# CarteCapteurAvant3.net
KiCad netlist of a schematic drawn in Altium Designer
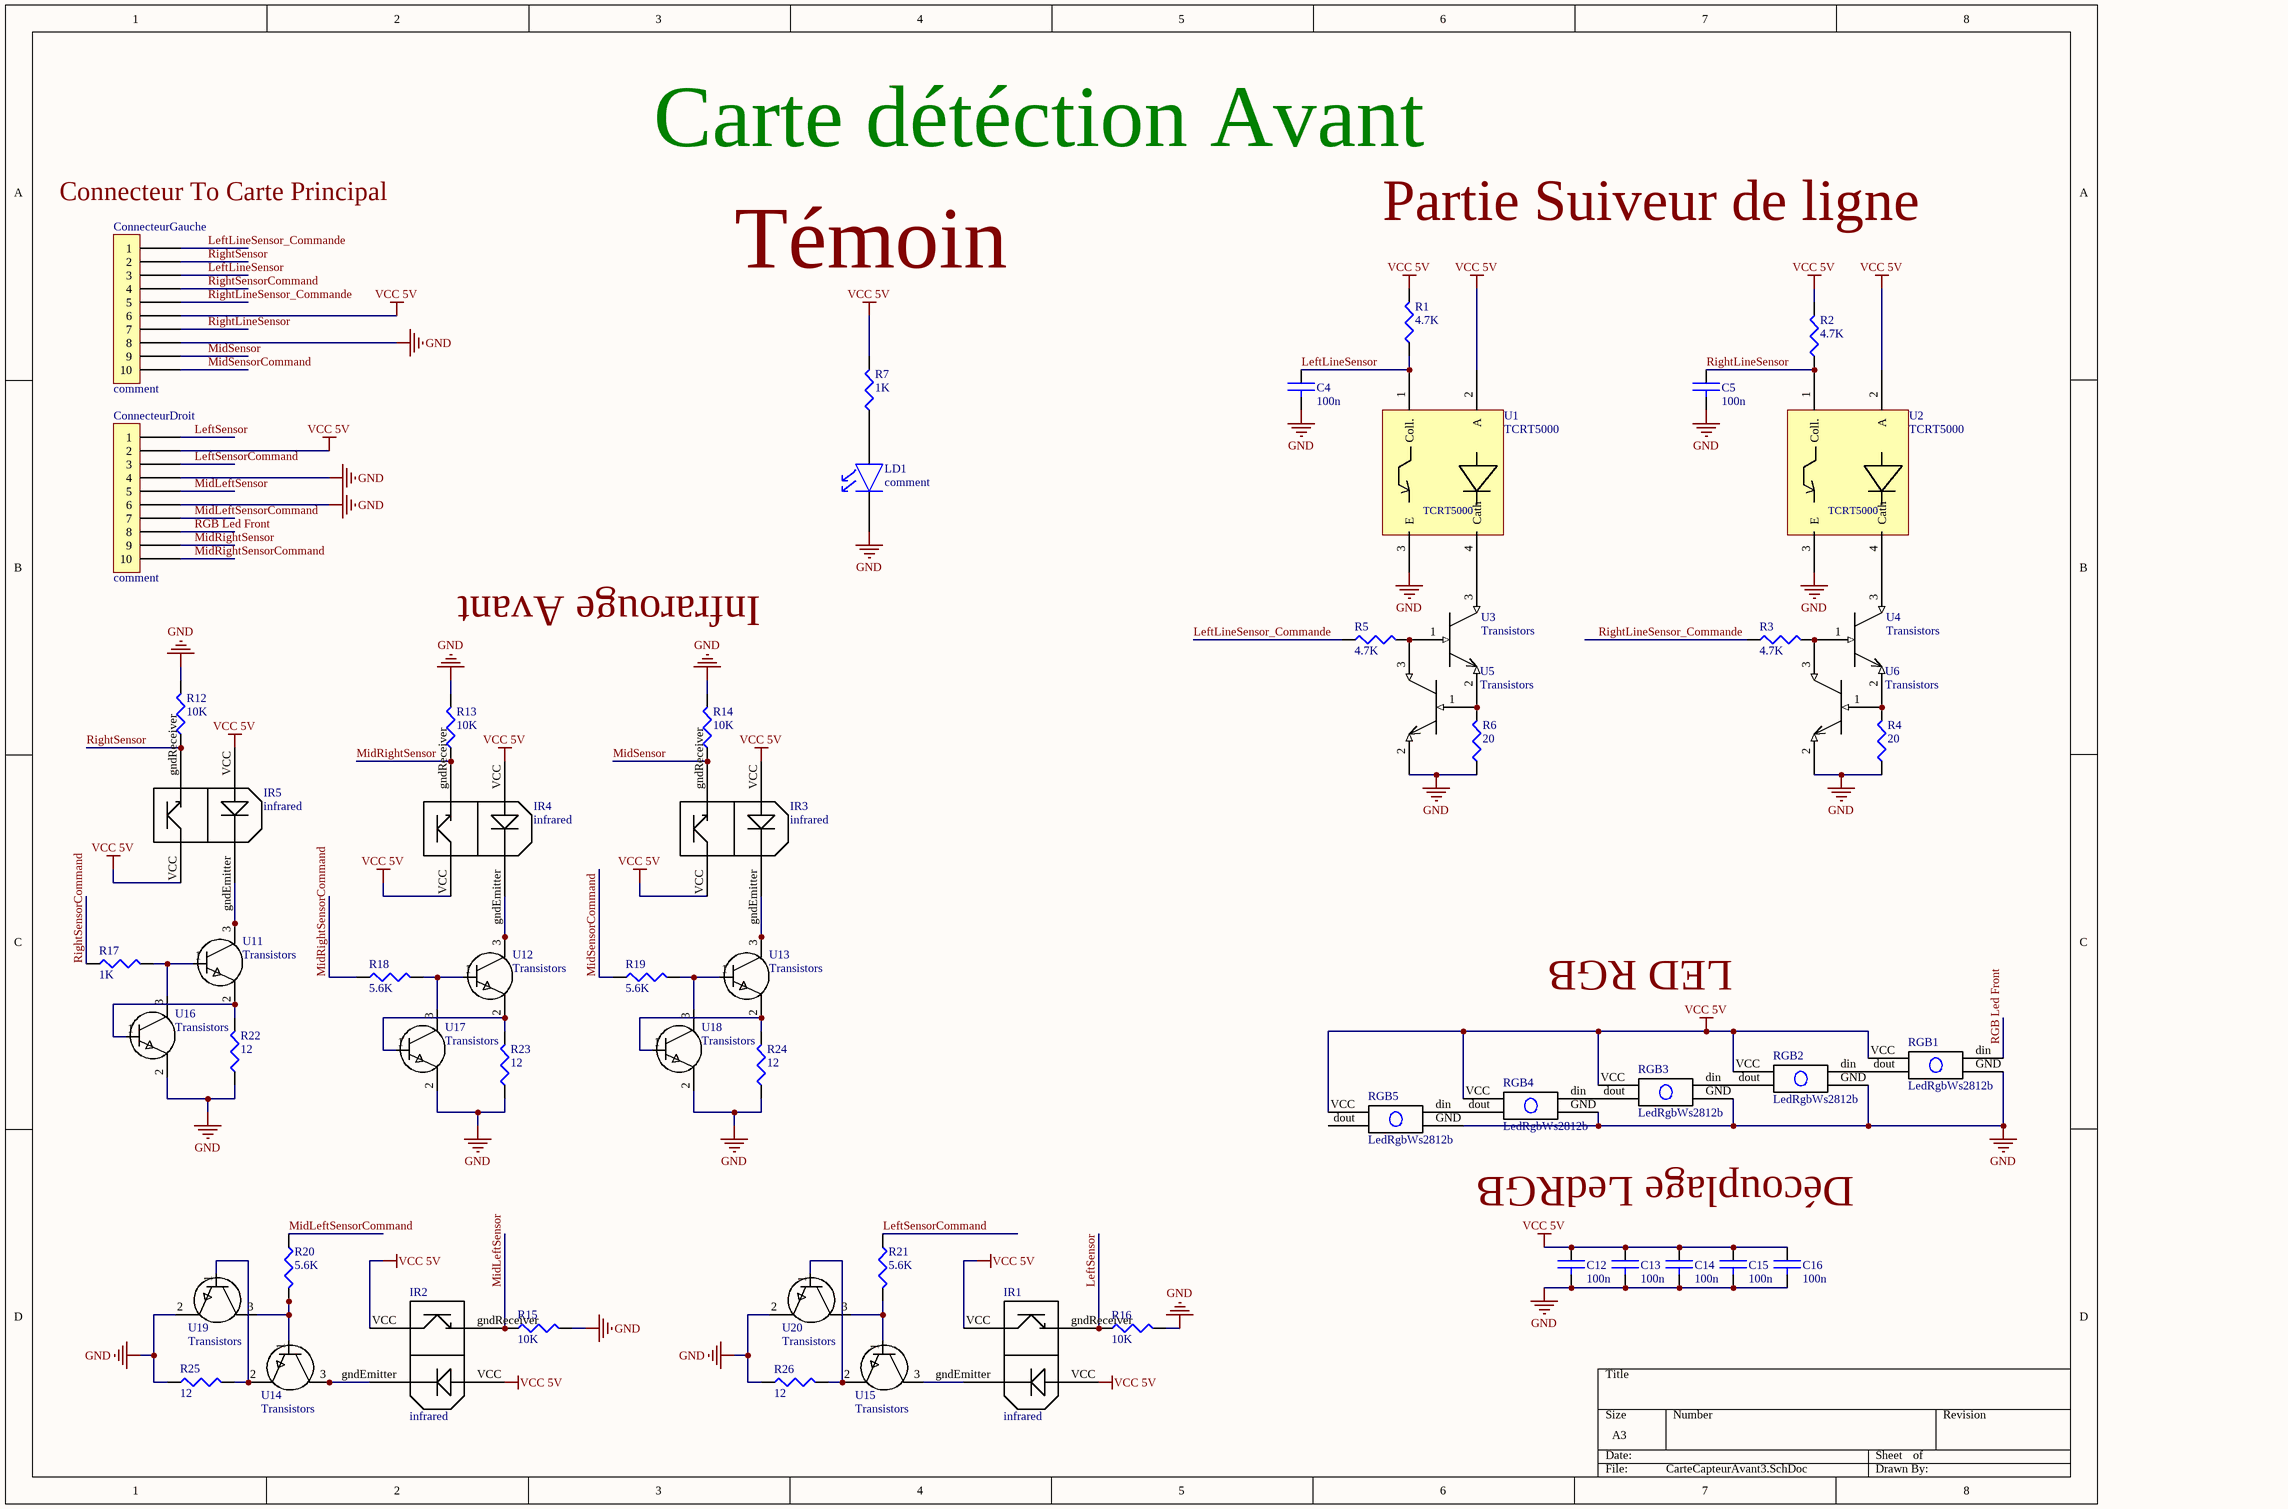
[diagram p0: CarteCapteurAvant3.SchDoc]

(export (version "E")
  (design (tool "Eeschema 10.0.6"))
  (components
    (comp (ref "C4")
      (value "100n")
      (footprint "0805")
      (description "capacité non polarisée")
      (fields (field (name "Comment") "CAP"))
      (libsource (lib "ISEN_basics_26-05-2015") (part "CAP"))
    )
    (comp (ref "C5")
      (value "100n")
      (footprint "0805")
      (description "capacité non polarisée")
      (fields (field (name "Comment") "CAP"))
      (libsource (lib "ISEN_basics_26-05-2015") (part "CAP"))
    )
    (comp (ref "C12")
      (value "100n")
      (footprint "0805")
      (description "capacité non polarisée")
      (fields (field (name "Comment") "CAP"))
      (libsource (lib "ISEN_basics_26-05-2015") (part "CAP"))
    )
    (comp (ref "C13")
      (value "100n")
      (footprint "0805")
      (description "capacité non polarisée")
      (fields (field (name "Comment") "CAP"))
      (libsource (lib "ISEN_basics_26-05-2015") (part "CAP"))
    )
    (comp (ref "C14")
      (value "100n")
      (footprint "0805")
      (description "capacité non polarisée")
      (fields (field (name "Comment") "CAP"))
      (libsource (lib "ISEN_basics_26-05-2015") (part "CAP"))
    )
    (comp (ref "C15")
      (value "100n")
      (footprint "0805")
      (description "capacité non polarisée")
      (fields (field (name "Comment") "CAP"))
      (libsource (lib "ISEN_basics_26-05-2015") (part "CAP"))
    )
    (comp (ref "C16")
      (value "100n")
      (footprint "0805")
      (description "capacité non polarisée")
      (fields (field (name "Comment") "CAP"))
      (libsource (lib "ISEN_basics_26-05-2015") (part "CAP"))
    )
    (comp (ref "ConnecteurDroit")
      (value "comment")
      (footprint "HE10-10V")
      (description "10-pin connector")
      (libsource (lib "ISEN_basics_26-05-2015") (part "HE10-10"))
    )
    (comp (ref "ConnecteurGauche")
      (value "comment")
      (footprint "HE10-10V")
      (description "10-pin connector")
      (libsource (lib "ISEN_basics_26-05-2015") (part "HE10-10"))
    )
    (comp (ref "IR1")
      (value "infrared")
      (footprint "Infrared")
      (libsource (lib "infrared") (part "RPR-359F"))
    )
    (comp (ref "IR2")
      (value "infrared")
      (footprint "Infrared")
      (libsource (lib "infrared") (part "RPR-359F"))
    )
    (comp (ref "IR3")
      (value "infrared")
      (footprint "Infrared")
      (libsource (lib "infrared") (part "RPR-359F"))
    )
    (comp (ref "IR4")
      (value "infrared")
      (footprint "Infrared")
      (libsource (lib "infrared") (part "RPR-359F"))
    )
    (comp (ref "IR5")
      (value "infrared")
      (footprint "Infrared")
      (libsource (lib "infrared") (part "RPR-359F"))
    )
    (comp (ref "LD1")
      (value "comment")
      (footprint "LED1206")
      (description "LED 5mm/3mm/CMS")
      (libsource (lib "ISEN_basics_26-05-2015") (part "LED"))
    )
    (comp (ref "R1")
      (value "4.7K")
      (footprint "0805")
      (description "resistance")
      (fields (field (name "Comment") "RES"))
      (libsource (lib "ISEN_basics_26-05-2015") (part "RES"))
    )
    (comp (ref "R2")
      (value "4.7K")
      (footprint "0805")
      (description "resistance")
      (fields (field (name "Comment") "RES"))
      (libsource (lib "ISEN_basics_26-05-2015") (part "RES"))
    )
    (comp (ref "R3")
      (value "4.7K")
      (footprint "0805")
      (description "resistance")
      (fields (field (name "Comment") "RES"))
      (libsource (lib "ISEN_basics_26-05-2015") (part "RES"))
    )
    (comp (ref "R4")
      (value "20")
      (footprint "0805")
      (description "resistance")
      (fields (field (name "Comment") "RES"))
      (libsource (lib "ISEN_basics_26-05-2015") (part "RES"))
    )
    (comp (ref "R5")
      (value "4.7K")
      (footprint "0805")
      (description "resistance")
      (fields (field (name "Comment") "RES"))
      (libsource (lib "ISEN_basics_26-05-2015") (part "RES"))
    )
    (comp (ref "R6")
      (value "20")
      (footprint "0805")
      (description "resistance")
      (fields (field (name "Comment") "RES"))
      (libsource (lib "ISEN_basics_26-05-2015") (part "RES"))
    )
    (comp (ref "R7")
      (value "1K")
      (footprint "0805")
      (description "resistance")
      (fields (field (name "Comment") "RES"))
      (libsource (lib "ISEN_basics_26-05-2015") (part "RES"))
    )
    (comp (ref "R12")
      (value "10K")
      (footprint "0805")
      (description "resistance")
      (fields (field (name "Comment") "RES"))
      (libsource (lib "ISEN_basics_26-05-2015") (part "RES"))
    )
    (comp (ref "R13")
      (value "10K")
      (footprint "0805")
      (description "resistance")
      (fields (field (name "Comment") "RES"))
      (libsource (lib "ISEN_basics_26-05-2015") (part "RES"))
    )
    (comp (ref "R14")
      (value "10K")
      (footprint "0805")
      (description "resistance")
      (fields (field (name "Comment") "RES"))
      (libsource (lib "ISEN_basics_26-05-2015") (part "RES"))
    )
    (comp (ref "R15")
      (value "10K")
      (footprint "0805")
      (description "resistance")
      (fields (field (name "Comment") "RES"))
      (libsource (lib "ISEN_basics_26-05-2015") (part "RES"))
    )
    (comp (ref "R16")
      (value "10K")
      (footprint "0805")
      (description "resistance")
      (fields (field (name "Comment") "RES"))
      (libsource (lib "ISEN_basics_26-05-2015") (part "RES"))
    )
    (comp (ref "R17")
      (value "1K")
      (footprint "0805")
      (description "resistance")
      (fields (field (name "Comment") "RES"))
      (libsource (lib "ISEN_basics_26-05-2015") (part "RES"))
    )
    (comp (ref "R18")
      (value "5.6K")
      (footprint "0805")
      (description "resistance")
      (fields (field (name "Comment") "RES"))
      (libsource (lib "ISEN_basics_26-05-2015") (part "RES"))
    )
    (comp (ref "R19")
      (value "5.6K")
      (footprint "0805")
      (description "resistance")
      (fields (field (name "Comment") "RES"))
      (libsource (lib "ISEN_basics_26-05-2015") (part "RES"))
    )
    (comp (ref "R20")
      (value "5.6K")
      (footprint "0805")
      (description "resistance")
      (fields (field (name "Comment") "RES"))
      (libsource (lib "ISEN_basics_26-05-2015") (part "RES"))
    )
    (comp (ref "R21")
      (value "5.6K")
      (footprint "0805")
      (description "resistance")
      (fields (field (name "Comment") "RES"))
      (libsource (lib "ISEN_basics_26-05-2015") (part "RES"))
    )
    (comp (ref "R22")
      (value "12")
      (footprint "0805")
      (description "resistance")
      (fields (field (name "Comment") "RES"))
      (libsource (lib "ISEN_basics_26-05-2015") (part "RES"))
    )
    (comp (ref "R23")
      (value "12")
      (footprint "0805")
      (description "resistance")
      (fields (field (name "Comment") "RES"))
      (libsource (lib "ISEN_basics_26-05-2015") (part "RES"))
    )
    (comp (ref "R24")
      (value "12")
      (footprint "0805")
      (description "resistance")
      (fields (field (name "Comment") "RES"))
      (libsource (lib "ISEN_basics_26-05-2015") (part "RES"))
    )
    (comp (ref "R25")
      (value "12")
      (footprint "0805")
      (description "resistance")
      (fields (field (name "Comment") "RES"))
      (libsource (lib "ISEN_basics_26-05-2015") (part "RES"))
    )
    (comp (ref "R26")
      (value "12")
      (footprint "0805")
      (description "resistance")
      (fields (field (name "Comment") "RES"))
      (libsource (lib "ISEN_basics_26-05-2015") (part "RES"))
    )
    (comp (ref "RGB1")
      (value "LedRgbWs2812b")
      (footprint "LedRgbWs2812b")
      (libsource (lib "LedRgbWs2812b") (part "LedRgbWs2812b"))
    )
    (comp (ref "RGB2")
      (value "LedRgbWs2812b")
      (footprint "LedRgbWs2812b")
      (libsource (lib "LedRgbWs2812b") (part "LedRgbWs2812b"))
    )
    (comp (ref "RGB3")
      (value "LedRgbWs2812b")
      (footprint "LedRgbWs2812b")
      (libsource (lib "LedRgbWs2812b") (part "LedRgbWs2812b"))
    )
    (comp (ref "RGB4")
      (value "LedRgbWs2812b")
      (footprint "LedRgbWs2812b")
      (libsource (lib "LedRgbWs2812b") (part "LedRgbWs2812b"))
    )
    (comp (ref "RGB5")
      (value "LedRgbWs2812b")
      (footprint "LedRgbWs2812b")
      (libsource (lib "LedRgbWs2812b") (part "LedRgbWs2812b"))
    )
    (comp (ref "U1")
      (value "TCRT5000")
      (footprint "TCRT5000 Droit")
      (libsource (lib "TCRT5000") (part "TCRT5000"))
    )
    (comp (ref "U2")
      (value "TCRT5000")
      (footprint "TCRT5000 Droit")
      (libsource (lib "TCRT5000") (part "TCRT5000"))
    )
    (comp (ref "U3") (value "Transistors") (footprint "BC817-40") (libsource (lib "") (part "Transistors_2")))
    (comp (ref "U4") (value "Transistors") (footprint "BC817-40") (libsource (lib "") (part "Transistors_2")))
    (comp (ref "U5") (value "Transistors") (footprint "BC817-40") (libsource (lib "") (part "Transistors_2")))
    (comp (ref "U6") (value "Transistors") (footprint "BC817-40") (libsource (lib "") (part "Transistors_2")))
    (comp (ref "U11")
      (value "Transistors")
      (footprint "BC817-40")
      (description "NPN transistor")
      (libsource (lib "") (part "Transistors_1"))
    )
    (comp (ref "U12")
      (value "Transistors")
      (footprint "BC817-40")
      (description "NPN transistor")
      (libsource (lib "") (part "Transistors_1"))
    )
    (comp (ref "U13")
      (value "Transistors")
      (footprint "BC817-40")
      (description "NPN transistor")
      (libsource (lib "") (part "Transistors_1"))
    )
    (comp (ref "U14")
      (value "Transistors")
      (footprint "BC817-40")
      (description "NPN transistor")
      (libsource (lib "Transistors") (part "Transistors"))
    )
    (comp (ref "U15")
      (value "Transistors")
      (footprint "BC817-40")
      (description "NPN transistor")
      (libsource (lib "Transistors") (part "Transistors"))
    )
    (comp (ref "U16")
      (value "Transistors")
      (footprint "BC817-40")
      (description "NPN transistor")
      (libsource (lib "") (part "Transistors_1"))
    )
    (comp (ref "U17")
      (value "Transistors")
      (footprint "BC817-40")
      (description "NPN transistor")
      (libsource (lib "") (part "Transistors_1"))
    )
    (comp (ref "U18")
      (value "Transistors")
      (footprint "BC817-40")
      (description "NPN transistor")
      (libsource (lib "") (part "Transistors_1"))
    )
    (comp (ref "U19")
      (value "Transistors")
      (footprint "BC817-40")
      (description "NPN transistor")
      (libsource (lib "Transistors") (part "Transistors"))
    )
    (comp (ref "U20")
      (value "Transistors")
      (footprint "BC817-40")
      (description "NPN transistor")
      (libsource (lib "Transistors") (part "Transistors"))
    )
  )
  (nets
    (net (code "1") (name "/LeftLineSensor") (class "Default")
      (node (ref "C4") (pin "1") (pinfunction "1_1") (pintype "passive"))
      (node (ref "ConnecteurGauche") (pin "3") (pinfunction "3_3") (pintype "passive"))
      (node (ref "R1") (pin "1") (pintype "passive"))
      (node (ref "U1") (pin "1") (pinfunction "Coll._1") (pintype "passive"))
    )
    (net (code "2") (name "/LeftLineSensor_Commande") (class "Default")
      (node (ref "ConnecteurGauche") (pin "1") (pinfunction "1_1") (pintype "passive"))
      (node (ref "R5") (pin "1") (pintype "passive"))
    )
    (net (code "3") (name "/LeftSensor") (class "Default")
      (node (ref "ConnecteurDroit") (pin "1") (pinfunction "1_1") (pintype "passive"))
      (node (ref "IR1") (pin "gndReceiver") (pinfunction "gndReceiver_gndReceiver") (pintype "passive"))
      (node (ref "R16") (pin "1") (pintype "passive"))
    )
    (net (code "4") (name "/LeftSensorCommand") (class "Default")
      (node (ref "ConnecteurDroit") (pin "3") (pinfunction "3_3") (pintype "passive"))
      (node (ref "R21") (pin "1") (pintype "passive"))
    )
    (net (code "5") (name "/MidLeftSensor") (class "Default")
      (node (ref "ConnecteurDroit") (pin "5") (pinfunction "5_5") (pintype "passive"))
      (node (ref "IR2") (pin "gndReceiver") (pinfunction "gndReceiver_gndReceiver") (pintype "passive"))
      (node (ref "R15") (pin "1") (pintype "passive"))
    )
    (net (code "6") (name "/MidLeftSensorCommand") (class "Default")
      (node (ref "ConnecteurDroit") (pin "7") (pinfunction "7_7") (pintype "passive"))
      (node (ref "R20") (pin "1") (pintype "passive"))
    )
    (net (code "7") (name "/MidRightSensor") (class "Default")
      (node (ref "ConnecteurDroit") (pin "9") (pinfunction "9_9") (pintype "passive"))
      (node (ref "IR4") (pin "gndReceiver") (pinfunction "gndReceiver_gndReceiver") (pintype "passive"))
      (node (ref "R13") (pin "1") (pintype "passive"))
    )
    (net (code "8") (name "/MidRightSensorCommand") (class "Default")
      (node (ref "ConnecteurDroit") (pin "10") (pinfunction "10_10") (pintype "passive"))
      (node (ref "R18") (pin "1") (pintype "passive"))
    )
    (net (code "9") (name "/MidSensor") (class "Default")
      (node (ref "ConnecteurGauche") (pin "9") (pinfunction "9_9") (pintype "passive"))
      (node (ref "IR3") (pin "gndReceiver") (pinfunction "gndReceiver_gndReceiver") (pintype "passive"))
      (node (ref "R14") (pin "1") (pintype "passive"))
    )
    (net (code "10") (name "/MidSensorCommand") (class "Default")
      (node (ref "ConnecteurGauche") (pin "10") (pinfunction "10_10") (pintype "passive"))
      (node (ref "R19") (pin "1") (pintype "passive"))
    )
    (net (code "11") (name "/RGB Led Front") (class "Default")
      (node (ref "ConnecteurDroit") (pin "8") (pinfunction "8_8") (pintype "passive"))
      (node (ref "RGB1") (pin "din") (pinfunction "din_din") (pintype "passive"))
    )
    (net (code "12") (name "/RightLineSensor") (class "Default")
      (node (ref "C5") (pin "1") (pinfunction "1_1") (pintype "passive"))
      (node (ref "ConnecteurGauche") (pin "7") (pinfunction "7_7") (pintype "passive"))
      (node (ref "R2") (pin "1") (pintype "passive"))
      (node (ref "U2") (pin "1") (pinfunction "Coll._1") (pintype "passive"))
    )
    (net (code "13") (name "/RightLineSensor_Commande") (class "Default")
      (node (ref "ConnecteurGauche") (pin "5") (pinfunction "5_5") (pintype "passive"))
      (node (ref "R3") (pin "1") (pintype "passive"))
    )
    (net (code "14") (name "/RightSensor") (class "Default")
      (node (ref "ConnecteurGauche") (pin "2") (pinfunction "2_2") (pintype "passive"))
      (node (ref "IR5") (pin "gndReceiver") (pinfunction "gndReceiver_gndReceiver") (pintype "passive"))
      (node (ref "R12") (pin "1") (pintype "passive"))
    )
    (net (code "15") (name "/RightSensorCommand") (class "Default")
      (node (ref "ConnecteurGauche") (pin "4") (pinfunction "4_4") (pintype "passive"))
      (node (ref "R17") (pin "1") (pintype "passive"))
    )
    (net (code "16") (name "GND") (class "Default")
      (node (ref "C12") (pin "2") (pinfunction "2_2") (pintype "passive"))
      (node (ref "C13") (pin "2") (pinfunction "2_2") (pintype "passive"))
      (node (ref "C14") (pin "2") (pinfunction "2_2") (pintype "passive"))
      (node (ref "C15") (pin "2") (pinfunction "2_2") (pintype "passive"))
      (node (ref "C16") (pin "2") (pinfunction "2_2") (pintype "passive"))
      (node (ref "C4") (pin "2") (pinfunction "2_2") (pintype "passive"))
      (node (ref "C5") (pin "2") (pinfunction "2_2") (pintype "passive"))
      (node (ref "ConnecteurDroit") (pin "4") (pinfunction "4_4") (pintype "passive"))
      (node (ref "ConnecteurDroit") (pin "6") (pinfunction "6_6") (pintype "passive"))
      (node (ref "ConnecteurGauche") (pin "8") (pinfunction "8_8") (pintype "passive"))
      (node (ref "LD1") (pin "K") (pinfunction "10_K") (pintype "passive"))
      (node (ref "R12") (pin "2") (pintype "passive"))
      (node (ref "R13") (pin "2") (pintype "passive"))
      (node (ref "R14") (pin "2") (pintype "passive"))
      (node (ref "R15") (pin "2") (pintype "passive"))
      (node (ref "R16") (pin "2") (pintype "passive"))
      (node (ref "R22") (pin "1") (pintype "passive"))
      (node (ref "R23") (pin "1") (pintype "passive"))
      (node (ref "R24") (pin "1") (pintype "passive"))
      (node (ref "R25") (pin "1") (pintype "passive"))
      (node (ref "R26") (pin "1") (pintype "passive"))
      (node (ref "R4") (pin "1") (pintype "passive"))
      (node (ref "R6") (pin "1") (pintype "passive"))
      (node (ref "RGB1") (pin "GND") (pinfunction "GND_GND") (pintype "passive"))
      (node (ref "RGB2") (pin "GND") (pinfunction "GND_GND") (pintype "passive"))
      (node (ref "RGB3") (pin "GND") (pinfunction "GND_GND") (pintype "passive"))
      (node (ref "RGB4") (pin "GND") (pinfunction "GND_GND") (pintype "passive"))
      (node (ref "RGB5") (pin "GND") (pinfunction "GND_GND") (pintype "passive"))
      (node (ref "U1") (pin "3") (pinfunction "E_3") (pintype "passive"))
      (node (ref "U16") (pin "2") (pinfunction "Emi_2") (pintype "passive"))
      (node (ref "U17") (pin "2") (pinfunction "Emi_2") (pintype "passive"))
      (node (ref "U18") (pin "2") (pinfunction "Emi_2") (pintype "passive"))
      (node (ref "U19") (pin "2") (pinfunction "Emi_2") (pintype "passive"))
      (node (ref "U2") (pin "3") (pinfunction "E_3") (pintype "passive"))
      (node (ref "U20") (pin "2") (pinfunction "Emi_2") (pintype "passive"))
      (node (ref "U5") (pin "2") (pinfunction "Emiter_2") (pintype "input"))
      (node (ref "U6") (pin "2") (pinfunction "Emiter_2") (pintype "input"))
    )
    (net (code "17") (name "Net-(LD1-8)") (class "Default")
      (node (ref "LD1") (pin "A") (pinfunction "8_A") (pintype "passive"))
      (node (ref "R7") (pin "1") (pintype "passive"))
    )
    (net (code "18") (name "Net-(RGB1-Paddout)") (class "Default")
      (node (ref "RGB1") (pin "dout") (pinfunction "dout_dout") (pintype "passive"))
      (node (ref "RGB2") (pin "din") (pinfunction "din_din") (pintype "passive"))
    )
    (net (code "19") (name "Net-(RGB2-Paddout)") (class "Default")
      (node (ref "RGB2") (pin "dout") (pinfunction "dout_dout") (pintype "passive"))
      (node (ref "RGB3") (pin "din") (pinfunction "din_din") (pintype "passive"))
    )
    (net (code "20") (name "Net-(RGB3-Paddout)") (class "Default")
      (node (ref "RGB3") (pin "dout") (pinfunction "dout_dout") (pintype "passive"))
      (node (ref "RGB4") (pin "din") (pinfunction "din_din") (pintype "passive"))
    )
    (net (code "21") (name "Net-(RGB4-Paddout)") (class "Default")
      (node (ref "RGB4") (pin "dout") (pinfunction "dout_dout") (pintype "passive"))
      (node (ref "RGB5") (pin "din") (pinfunction "din_din") (pintype "passive"))
    )
    (net (code "22") (name "Net-(U1-Cath)") (class "Default")
      (node (ref "U1") (pin "4") (pinfunction "Cath_4") (pintype "passive"))
      (node (ref "U3") (pin "3") (pinfunction "Collector_3") (pintype "input"))
    )
    (net (code "23") (name "Net-(U2-Cath)") (class "Default")
      (node (ref "U2") (pin "4") (pinfunction "Cath_4") (pintype "passive"))
      (node (ref "U4") (pin "3") (pinfunction "Collector_3") (pintype "input"))
    )
    (net (code "24") (name "Net-(U3-Base)") (class "Default")
      (node (ref "R5") (pin "2") (pintype "passive"))
      (node (ref "U3") (pin "1") (pinfunction "Base_1") (pintype "input"))
      (node (ref "U5") (pin "3") (pinfunction "Collector_3") (pintype "input"))
    )
    (net (code "25") (name "Net-(U3-Emiter)") (class "Default")
      (node (ref "R6") (pin "2") (pintype "passive"))
      (node (ref "U3") (pin "2") (pinfunction "Emiter_2") (pintype "input"))
      (node (ref "U5") (pin "1") (pinfunction "Base_1") (pintype "input"))
    )
    (net (code "26") (name "Net-(U4-Base)") (class "Default")
      (node (ref "R3") (pin "2") (pintype "passive"))
      (node (ref "U4") (pin "1") (pinfunction "Base_1") (pintype "input"))
      (node (ref "U6") (pin "3") (pinfunction "Collector_3") (pintype "input"))
    )
    (net (code "27") (name "Net-(U4-Emiter)") (class "Default")
      (node (ref "R4") (pin "2") (pintype "passive"))
      (node (ref "U4") (pin "2") (pinfunction "Emiter_2") (pintype "input"))
      (node (ref "U6") (pin "1") (pinfunction "Base_1") (pintype "input"))
    )
    (net (code "28") (name "Net-(U11-Base)") (class "Default")
      (node (ref "R17") (pin "2") (pintype "passive"))
      (node (ref "U11") (pin "1") (pinfunction "Base_1") (pintype "passive"))
      (node (ref "U16") (pin "3") (pinfunction "Co_3") (pintype "passive"))
    )
    (net (code "29") (name "Net-(U11-Co)") (class "Default")
      (node (ref "IR5") (pin "gndEmitter") (pinfunction "gndEmitter_gndEmitter") (pintype "passive"))
      (node (ref "U11") (pin "3") (pinfunction "Co_3") (pintype "passive"))
    )
    (net (code "30") (name "Net-(U11-Emi)") (class "Default")
      (node (ref "R22") (pin "2") (pintype "passive"))
      (node (ref "U11") (pin "2") (pinfunction "Emi_2") (pintype "passive"))
      (node (ref "U16") (pin "1") (pinfunction "Base_1") (pintype "passive"))
    )
    (net (code "31") (name "Net-(U12-Base)") (class "Default")
      (node (ref "R18") (pin "2") (pintype "passive"))
      (node (ref "U12") (pin "1") (pinfunction "Base_1") (pintype "passive"))
      (node (ref "U17") (pin "3") (pinfunction "Co_3") (pintype "passive"))
    )
    (net (code "32") (name "Net-(U12-Co)") (class "Default")
      (node (ref "IR4") (pin "gndEmitter") (pinfunction "gndEmitter_gndEmitter") (pintype "passive"))
      (node (ref "U12") (pin "3") (pinfunction "Co_3") (pintype "passive"))
    )
    (net (code "33") (name "Net-(U12-Emi)") (class "Default")
      (node (ref "R23") (pin "2") (pintype "passive"))
      (node (ref "U12") (pin "2") (pinfunction "Emi_2") (pintype "passive"))
      (node (ref "U17") (pin "1") (pinfunction "Base_1") (pintype "passive"))
    )
    (net (code "34") (name "Net-(U13-Base)") (class "Default")
      (node (ref "R19") (pin "2") (pintype "passive"))
      (node (ref "U13") (pin "1") (pinfunction "Base_1") (pintype "passive"))
      (node (ref "U18") (pin "3") (pinfunction "Co_3") (pintype "passive"))
    )
    (net (code "35") (name "Net-(U13-Co)") (class "Default")
      (node (ref "IR3") (pin "gndEmitter") (pinfunction "gndEmitter_gndEmitter") (pintype "passive"))
      (node (ref "U13") (pin "3") (pinfunction "Co_3") (pintype "passive"))
    )
    (net (code "36") (name "Net-(U13-Emi)") (class "Default")
      (node (ref "R24") (pin "2") (pintype "passive"))
      (node (ref "U13") (pin "2") (pinfunction "Emi_2") (pintype "passive"))
      (node (ref "U18") (pin "1") (pinfunction "Base_1") (pintype "passive"))
    )
    (net (code "37") (name "Net-(U14-Base)") (class "Default")
      (node (ref "R20") (pin "2") (pintype "passive"))
      (node (ref "U14") (pin "1") (pinfunction "Base_1") (pintype "passive"))
      (node (ref "U19") (pin "3") (pinfunction "Co_3") (pintype "passive"))
    )
    (net (code "38") (name "Net-(U14-Co)") (class "Default")
      (node (ref "IR2") (pin "gndEmitter") (pinfunction "gndEmitter_gndEmitter") (pintype "passive"))
      (node (ref "U14") (pin "3") (pinfunction "Co_3") (pintype "passive"))
    )
    (net (code "39") (name "Net-(U14-Emi)") (class "Default")
      (node (ref "R25") (pin "2") (pintype "passive"))
      (node (ref "U14") (pin "2") (pinfunction "Emi_2") (pintype "passive"))
      (node (ref "U19") (pin "1") (pinfunction "Base_1") (pintype "passive"))
    )
    (net (code "40") (name "Net-(U15-Base)") (class "Default")
      (node (ref "R21") (pin "2") (pintype "passive"))
      (node (ref "U15") (pin "1") (pinfunction "Base_1") (pintype "passive"))
      (node (ref "U20") (pin "3") (pinfunction "Co_3") (pintype "passive"))
    )
    (net (code "41") (name "Net-(U15-Co)") (class "Default")
      (node (ref "IR1") (pin "gndEmitter") (pinfunction "gndEmitter_gndEmitter") (pintype "passive"))
      (node (ref "U15") (pin "3") (pinfunction "Co_3") (pintype "passive"))
    )
    (net (code "42") (name "Net-(U15-Emi)") (class "Default")
      (node (ref "R26") (pin "2") (pintype "passive"))
      (node (ref "U15") (pin "2") (pinfunction "Emi_2") (pintype "passive"))
      (node (ref "U20") (pin "1") (pinfunction "Base_1") (pintype "passive"))
    )
    (net (code "43") (name "VCC 5V") (class "Default")
      (node (ref "C12") (pin "1") (pinfunction "1_1") (pintype "passive"))
      (node (ref "C13") (pin "1") (pinfunction "1_1") (pintype "passive"))
      (node (ref "C14") (pin "1") (pinfunction "1_1") (pintype "passive"))
      (node (ref "C15") (pin "1") (pinfunction "1_1") (pintype "passive"))
      (node (ref "C16") (pin "1") (pinfunction "1_1") (pintype "passive"))
      (node (ref "ConnecteurDroit") (pin "2") (pinfunction "2_2") (pintype "passive"))
      (node (ref "ConnecteurGauche") (pin "6") (pinfunction "6_6") (pintype "passive"))
      (node (ref "IR1") (pin "VCC") (pinfunction "VCC_VCC") (pintype "passive"))
      (node (ref "IR2") (pin "VCC") (pinfunction "VCC_VCC") (pintype "passive"))
      (node (ref "IR3") (pin "VCC") (pinfunction "VCC_VCC") (pintype "passive"))
      (node (ref "IR4") (pin "VCC") (pinfunction "VCC_VCC") (pintype "passive"))
      (node (ref "IR5") (pin "VCC") (pinfunction "VCC_VCC") (pintype "passive"))
      (node (ref "R1") (pin "2") (pintype "passive"))
      (node (ref "R2") (pin "2") (pintype "passive"))
      (node (ref "R7") (pin "2") (pintype "passive"))
      (node (ref "RGB1") (pin "VCC") (pinfunction "VCC_VCC") (pintype "passive"))
      (node (ref "RGB2") (pin "VCC") (pinfunction "VCC_VCC") (pintype "passive"))
      (node (ref "RGB3") (pin "VCC") (pinfunction "VCC_VCC") (pintype "passive"))
      (node (ref "RGB4") (pin "VCC") (pinfunction "VCC_VCC") (pintype "passive"))
      (node (ref "RGB5") (pin "VCC") (pinfunction "VCC_VCC") (pintype "passive"))
      (node (ref "U1") (pin "2") (pinfunction "A_2") (pintype "passive"))
      (node (ref "U2") (pin "2") (pinfunction "A_2") (pintype "passive"))
    )
    (net (code "44") (name "unconnected-(RGB5-Paddout)") (class "Default")
      (node (ref "RGB5") (pin "dout") (pinfunction "dout_dout") (pintype "passive"))
    )
  )
)
